# loki.net
KiCad netlist of a schematic drawn in EAGLE
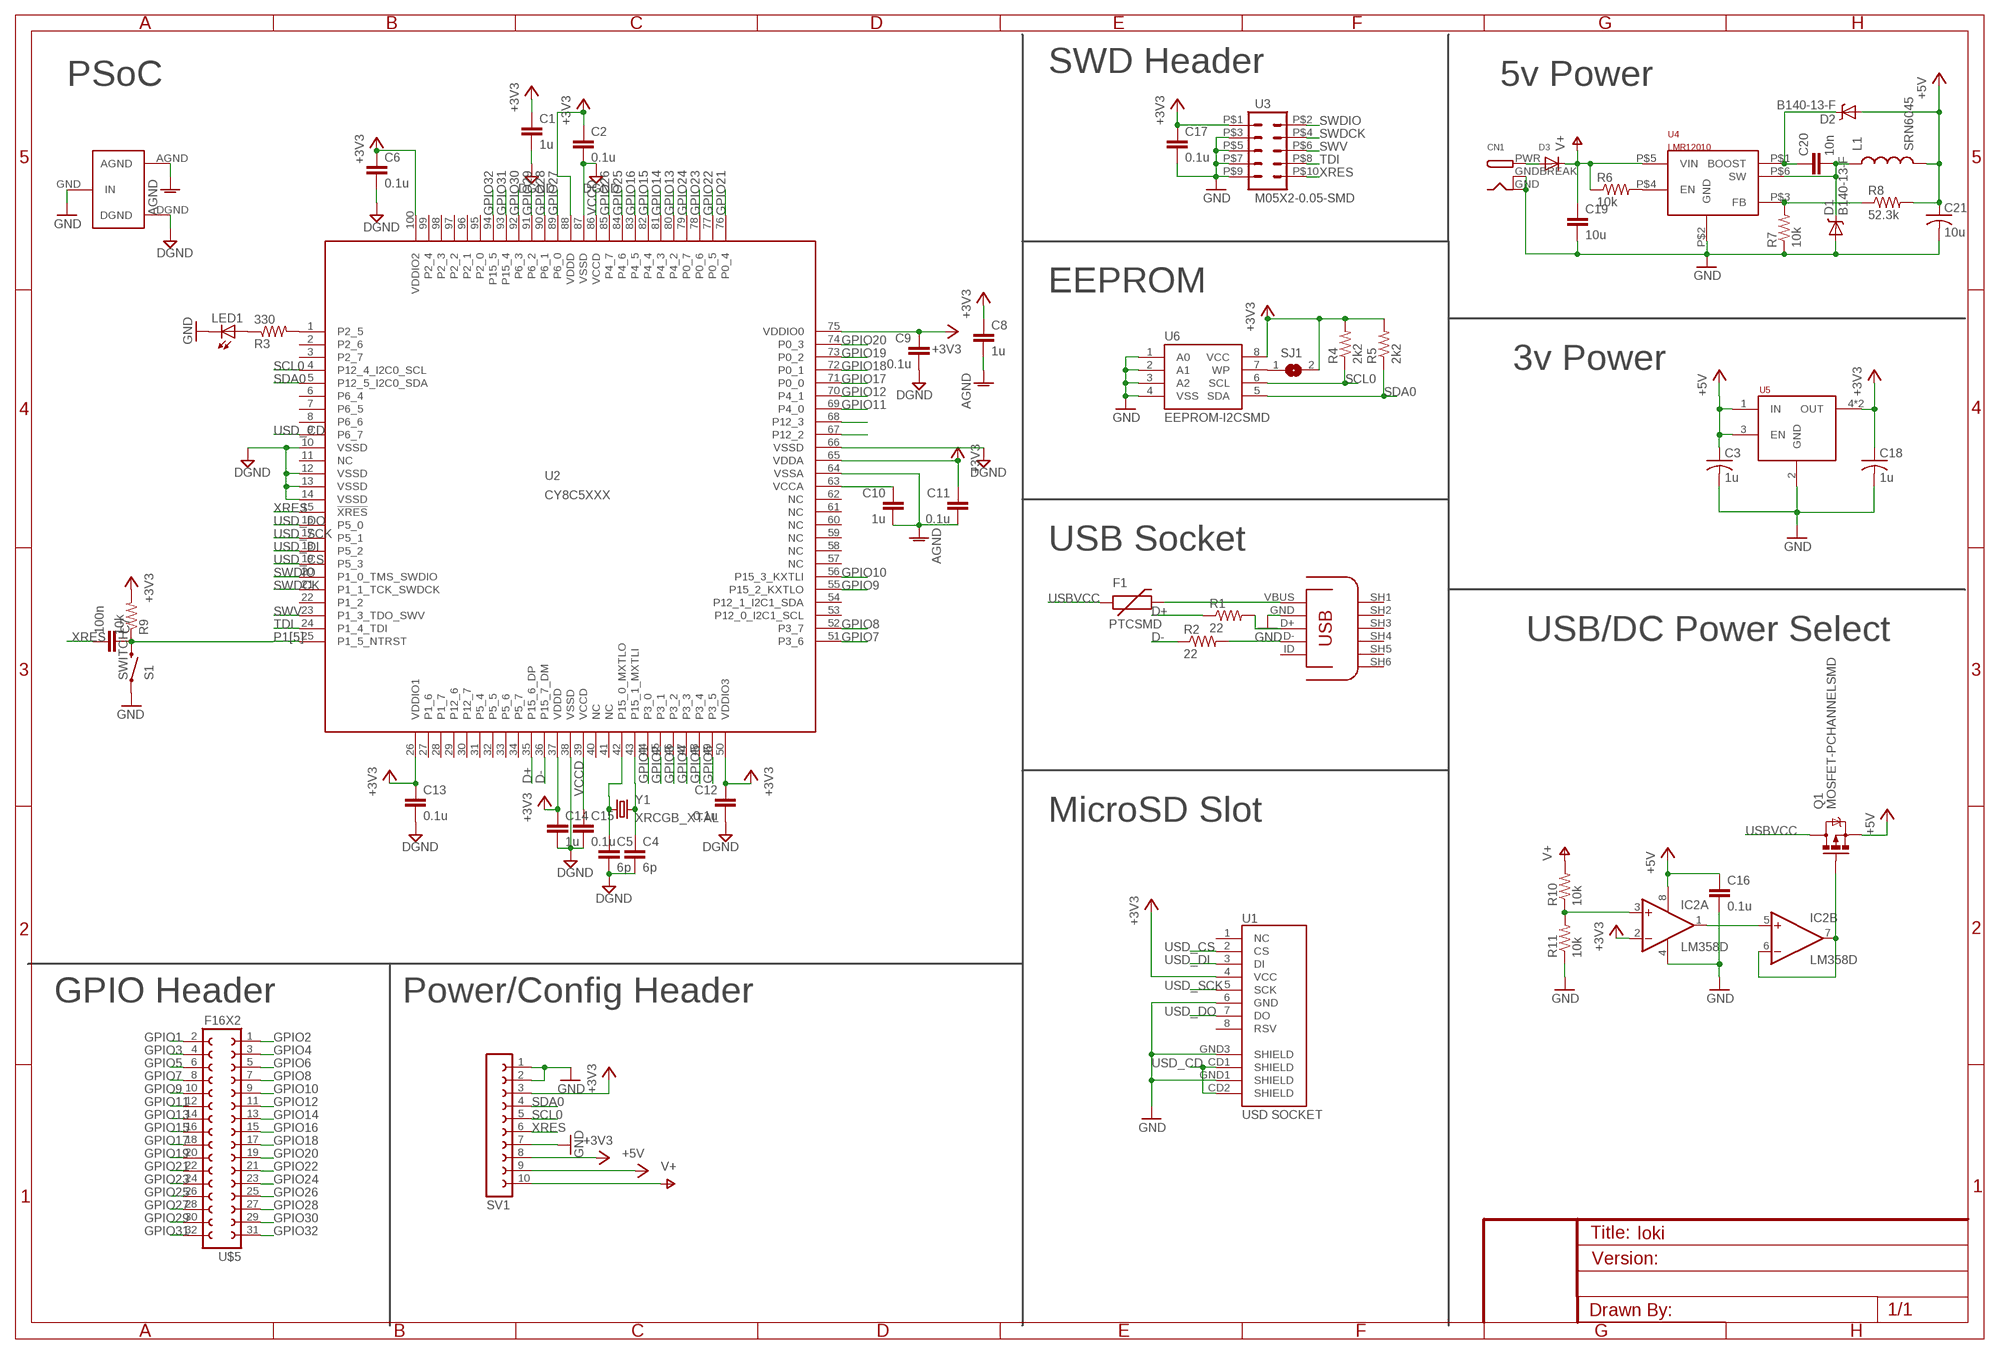
[diagram p0: schematic, sheet 1]

(export (version "E")
  (design (tool "Eeschema 10.0.6"))
  (components
    (comp (ref "C1")
      (value "1u")
      (footprint "eagle-import:C0603K")
      (libsource (lib "eagle-import") (part "C-EUC0603K"))
    )
    (comp (ref "C2")
      (value "0.1u")
      (footprint "eagle-import:C0603K")
      (libsource (lib "eagle-import") (part "C-EUC0603K"))
    )
    (comp (ref "C3")
      (value "1u")
      (footprint "eagle-import:C0603")
      (libsource (lib "eagle-import") (part "C-USC0603"))
    )
    (comp (ref "C4")
      (value "6p")
      (footprint "eagle-import:C0603K")
      (libsource (lib "eagle-import") (part "C-EUC0603K"))
    )
    (comp (ref "C5")
      (value "6p")
      (footprint "eagle-import:C0603K")
      (libsource (lib "eagle-import") (part "C-EUC0603K"))
    )
    (comp (ref "C6")
      (value "0.1u")
      (footprint "eagle-import:C0603K")
      (libsource (lib "eagle-import") (part "C-EUC0603K"))
    )
    (comp (ref "C7")
      (value "100n")
      (footprint "eagle-import:C0603K")
      (libsource (lib "eagle-import") (part "C-EUC0603K"))
    )
    (comp (ref "C8")
      (value "1u")
      (footprint "eagle-import:C0603K")
      (libsource (lib "eagle-import") (part "C-EUC0603K"))
    )
    (comp (ref "C9")
      (value "0.1u")
      (footprint "eagle-import:C0603K")
      (libsource (lib "eagle-import") (part "C-EUC0603K"))
    )
    (comp (ref "C10")
      (value "1u")
      (footprint "eagle-import:C0603K")
      (libsource (lib "eagle-import") (part "C-EUC0603K"))
    )
    (comp (ref "C11")
      (value "0.1u")
      (footprint "eagle-import:C0603K")
      (libsource (lib "eagle-import") (part "C-EUC0603K"))
    )
    (comp (ref "C12")
      (value "0.1u")
      (footprint "eagle-import:C0603K")
      (libsource (lib "eagle-import") (part "C-EUC0603K"))
    )
    (comp (ref "C13")
      (value "0.1u")
      (footprint "eagle-import:C0603K")
      (libsource (lib "eagle-import") (part "C-EUC0603K"))
    )
    (comp (ref "C14")
      (value "1u")
      (footprint "eagle-import:C0603K")
      (libsource (lib "eagle-import") (part "C-EUC0603K"))
    )
    (comp (ref "C15")
      (value "0.1u")
      (footprint "eagle-import:C0603K")
      (libsource (lib "eagle-import") (part "C-EUC0603K"))
    )
    (comp (ref "C16")
      (value "0.1u")
      (footprint "eagle-import:0603-CAP")
      (libsource (lib "eagle-import") (part "CAP0603-CAP"))
    )
    (comp (ref "C17")
      (value "0.1u")
      (footprint "eagle-import:C0603K")
      (libsource (lib "eagle-import") (part "C-EUC0603K"))
    )
    (comp (ref "C18")
      (value "1u")
      (footprint "eagle-import:C0603")
      (libsource (lib "eagle-import") (part "C-USC0603"))
    )
    (comp (ref "C19")
      (value "10u")
      (footprint "eagle-import:C1210")
      (libsource (lib "eagle-import") (part "C-EUC1210"))
    )
    (comp (ref "C20")
      (value "10n")
      (footprint "eagle-import:C0805")
      (libsource (lib "eagle-import") (part "C-EUC0805"))
    )
    (comp (ref "C21")
      (value "10u")
      (footprint "eagle-import:C1206")
      (libsource (lib "eagle-import") (part "C-USC1206"))
    )
    (comp (ref "CN1")
      (value "DCBARRELPTH")
      (footprint "eagle-import:DCJACK_2MM_PTH")
      (libsource (lib "eagle-import") (part "DCBARRELPTH"))
    )
    (comp (ref "D1")
      (value "B140-13-F")
      (footprint "eagle-import:SMA-DIODE")
      (libsource (lib "eagle-import") (part "DIODE-SCHOTTKY_"))
    )
    (comp (ref "D2")
      (value "B140-13-F")
      (footprint "eagle-import:SMA-DIODE")
      (libsource (lib "eagle-import") (part "DIODE-SCHOTTKY_"))
    )
    (comp (ref "D3")
      (value "DIODESMA")
      (footprint "eagle-import:SMADIODE")
      (libsource (lib "eagle-import") (part "DIODESMA"))
    )
    (comp (ref "F1")
      (value "PTCSMD")
      (footprint "eagle-import:PTC-1206")
      (libsource (lib "eagle-import") (part "PTCSMD"))
    )
    (comp (ref "IC2")
      (value "LM358D")
      (footprint "eagle-import:SO08")
      (libsource (lib "eagle-import") (part "LM358D"))
    )
    (comp (ref "L1")
      (value "SRN6045")
      (footprint "eagle-import:SRN6045")
      (libsource (lib "eagle-import") (part "SRN6045"))
    )
    (comp (ref "LED1")
      (value "LEDCHIP-LED0805")
      (footprint "eagle-import:CHIP-LED0805")
      (libsource (lib "eagle-import") (part "LEDCHIP-LED0805"))
    )
    (comp (ref "Q1")
      (value "MOSFET-PCHANNELSMD")
      (footprint "eagle-import:SOT23-3")
      (libsource (lib "eagle-import") (part "MOSFET-PCHANNELSMD"))
    )
    (comp (ref "R1")
      (value "22")
      (footprint "eagle-import:0603-RES")
      (libsource (lib "eagle-import") (part "RESISTOR0603-RES"))
    )
    (comp (ref "R2")
      (value "22")
      (footprint "eagle-import:0603-RES")
      (libsource (lib "eagle-import") (part "RESISTOR0603-RES"))
    )
    (comp (ref "R3")
      (value "330")
      (footprint "eagle-import:R0603")
      (libsource (lib "eagle-import") (part "R-US_R0603"))
    )
    (comp (ref "R4")
      (value "2k2")
      (footprint "eagle-import:R0603")
      (libsource (lib "eagle-import") (part "R-US_R0603"))
    )
    (comp (ref "R5")
      (value "2k2")
      (footprint "eagle-import:R0603")
      (libsource (lib "eagle-import") (part "R-US_R0603"))
    )
    (comp (ref "R6")
      (value "10k")
      (footprint "eagle-import:R0603")
      (libsource (lib "eagle-import") (part "R-US_R0603"))
    )
    (comp (ref "R7")
      (value "10k")
      (footprint "eagle-import:R0603")
      (libsource (lib "eagle-import") (part "R-US_R0603"))
    )
    (comp (ref "R8")
      (value "52.3k")
      (footprint "eagle-import:R0603")
      (libsource (lib "eagle-import") (part "R-US_R0603"))
    )
    (comp (ref "R9")
      (value "10k")
      (footprint "eagle-import:R0603")
      (libsource (lib "eagle-import") (part "R-US_R0603"))
    )
    (comp (ref "R10")
      (value "10k")
      (footprint "eagle-import:R0603")
      (libsource (lib "eagle-import") (part "R-US_R0603"))
    )
    (comp (ref "R11")
      (value "10k")
      (footprint "eagle-import:R0603")
      (libsource (lib "eagle-import") (part "R-US_R0603"))
    )
    (comp (ref "S1")
      (value "SWITCH")
      (footprint "eagle-import:TACTILE_SWITCH_SMD")
      (libsource (lib "eagle-import") (part "SWITCH-MOMENTARY-2SMD"))
    )
    (comp (ref "SJ1") (value "SJ") (footprint "eagle-import:SJ") (libsource (lib "eagle-import") (part "SJ")))
    (comp (ref "SV1")
      (value "FE10-1")
      (footprint "eagle-import:FE10")
      (libsource (lib "eagle-import") (part "FE10-1"))
    )
    (comp (ref "U$5")
      (value "F16X2")
      (footprint "eagle-import:FE16-2")
      (libsource (lib "eagle-import") (part "F16X2"))
    )
    (comp (ref "U$9")
      (value "GND_CONNECT")
      (footprint "eagle-import:GNDCONNECT")
      (libsource (lib "eagle-import") (part "GND_CONNECT"))
    )
    (comp (ref "U1")
      (value "USD SOCKET")
      (footprint "eagle-import:MICRO-SD-SOCKET-PP")
      (libsource (lib "eagle-import") (part "USD-SOCKETNEW"))
    )
    (comp (ref "U2")
      (value "CY8C5XXX")
      (footprint "eagle-import:TQFP-14X14-100")
      (fields (field (name "MPN") "CY8C5588AXI-060"))
      (libsource (lib "eagle-import") (part "CY8C5XXX-100PIN"))
    )
    (comp (ref "U3")
      (value "M05X2-0.05-SMD")
      (footprint "eagle-import:PINHD-2X5-0.05-SMD")
      (libsource (lib "eagle-import") (part "M05X2-0.05-SMD"))
    )
    (comp (ref "U4")
      (value "LMR12010")
      (footprint "eagle-import:TSOT-6")
      (libsource (lib "eagle-import") (part "LMR12010"))
    )
    (comp (ref "U5")
      (value "TLV702XX")
      (footprint "eagle-import:SOT23-5")
      (libsource (lib "eagle-import") (part "TLV702XX"))
    )
    (comp (ref "U6")
      (value "EEPROM-I2CSMD")
      (footprint "eagle-import:SO08")
      (libsource (lib "eagle-import") (part "EEPROM-I2CSMD"))
    )
    (comp (ref "U7")
      (value "MICROUSB")
      (footprint "eagle-import:USB-MICROB")
      (libsource (lib "eagle-import") (part "MICROUSB"))
    )
    (comp (ref "Y1")
      (value "XRCGB_XTAL")
      (footprint "eagle-import:XRCGB-XTAL")
      (libsource (lib "eagle-import") (part "XRCGB_XTAL"))
    )
  )
  (nets
    (net (code "1") (name "+3V3") (class "Default")
      (node (ref "C1") (pin "1") (pinfunction "1_1") (pintype "passive"))
      (node (ref "C11") (pin "1") (pinfunction "1_1") (pintype "passive"))
      (node (ref "C12") (pin "1") (pinfunction "1_1") (pintype "passive"))
      (node (ref "C13") (pin "1") (pinfunction "1_1") (pintype "passive"))
      (node (ref "C14") (pin "1") (pinfunction "1_1") (pintype "passive"))
      (node (ref "C17") (pin "1") (pinfunction "1_1") (pintype "passive"))
      (node (ref "C18") (pin "1") (pinfunction "1_1") (pintype "passive"))
      (node (ref "C2") (pin "1") (pinfunction "1_1") (pintype "passive"))
      (node (ref "C6") (pin "1") (pinfunction "1_1") (pintype "passive"))
      (node (ref "C8") (pin "1") (pinfunction "1_1") (pintype "passive"))
      (node (ref "C9") (pin "1") (pinfunction "1_1") (pintype "passive"))
      (node (ref "IC2") (pin "2") (pinfunction "-IN_2") (pintype "input"))
      (node (ref "R4") (pin "2") (pinfunction "2_2") (pintype "passive"))
      (node (ref "R5") (pin "2") (pinfunction "2_2") (pintype "passive"))
      (node (ref "R9") (pin "2") (pinfunction "2_2") (pintype "passive"))
      (node (ref "SJ1") (pin "2") (pinfunction "2_2") (pintype "passive"))
      (node (ref "SV1") (pin "3") (pinfunction "3_3") (pintype "passive"))
      (node (ref "SV1") (pin "8") (pinfunction "8_8") (pintype "passive"))
      (node (ref "U1") (pin "4") (pinfunction "VCC_4") (pintype "bidirectional"))
      (node (ref "U2") (pin "100") (pinfunction "VDDIO2_100") (pintype "passive"))
      (node (ref "U2") (pin "26") (pinfunction "VDDIO1_26") (pintype "passive"))
      (node (ref "U2") (pin "37") (pinfunction "VDDD_37") (pintype "passive"))
      (node (ref "U2") (pin "50") (pinfunction "VDDIO3_50") (pintype "passive"))
      (node (ref "U2") (pin "65") (pinfunction "VDDA_65") (pintype "passive"))
      (node (ref "U2") (pin "75") (pinfunction "VDDIO0_75") (pintype "passive"))
      (node (ref "U2") (pin "88") (pinfunction "VDDD_88") (pintype "passive"))
      (node (ref "U3") (pin "P$1") (pinfunction "1_P$1") (pintype "passive"))
      (node (ref "U5") (pin "4") (pinfunction "OUT_4") (pintype "power_in"))
      (node (ref "U5") (pin "5") (pinfunction "OUT_5") (pintype "power_in"))
      (node (ref "U6") (pin "8") (pinfunction "VCC_8") (pintype "power_in"))
    )
    (net (code "2") (name "+5V") (class "Default")
      (node (ref "C16") (pin "1") (pinfunction "1_1") (pintype "passive"))
      (node (ref "C21") (pin "1") (pinfunction "1_1") (pintype "passive"))
      (node (ref "C3") (pin "1") (pinfunction "1_1") (pintype "passive"))
      (node (ref "D2") (pin "A") (pinfunction "A_A") (pintype "passive"))
      (node (ref "IC2") (pin "8") (pinfunction "V+_8") (pintype "power_in"))
      (node (ref "L1") (pin "P$2") (pinfunction "2_P$2") (pintype "passive"))
      (node (ref "Q1") (pin "2") (pinfunction "S_2") (pintype "passive"))
      (node (ref "R8") (pin "2") (pinfunction "2_2") (pintype "passive"))
      (node (ref "SV1") (pin "9") (pinfunction "9_9") (pintype "passive"))
      (node (ref "U5") (pin "1") (pinfunction "IN_1") (pintype "power_in"))
      (node (ref "U5") (pin "3") (pinfunction "EN_3") (pintype "input"))
    )
    (net (code "3") (name "/D+") (class "Default")
      (node (ref "R1") (pin "1") (pinfunction "1_1") (pintype "passive"))
      (node (ref "U2") (pin "35") (pinfunction "P15_6_DP_35") (pintype "passive"))
    )
    (net (code "4") (name "/D-") (class "Default")
      (node (ref "R2") (pin "1") (pinfunction "1_1") (pintype "passive"))
      (node (ref "U2") (pin "36") (pinfunction "P15_7_DM_36") (pintype "passive"))
    )
    (net (code "5") (name "/GPIO1") (class "Default")
      (node (ref "U$5") (pin "2") (pinfunction "2_2") (pintype "passive"))
      (node (ref "U2") (pin "44") (pinfunction "P3_0_44") (pintype "passive"))
    )
    (net (code "6") (name "/GPIO2") (class "Default")
      (node (ref "U$5") (pin "1") (pinfunction "1_1") (pintype "passive"))
      (node (ref "U2") (pin "45") (pinfunction "P3_1_45") (pintype "passive"))
    )
    (net (code "7") (name "/GPIO3") (class "Default")
      (node (ref "U$5") (pin "4") (pinfunction "4_4") (pintype "passive"))
      (node (ref "U2") (pin "46") (pinfunction "P3_2_46") (pintype "passive"))
    )
    (net (code "8") (name "/GPIO4") (class "Default")
      (node (ref "U$5") (pin "3") (pinfunction "3_3") (pintype "passive"))
      (node (ref "U2") (pin "47") (pinfunction "P3_3_47") (pintype "passive"))
    )
    (net (code "9") (name "/GPIO5") (class "Default")
      (node (ref "U$5") (pin "6") (pinfunction "6_6") (pintype "passive"))
      (node (ref "U2") (pin "48") (pinfunction "P3_4_48") (pintype "passive"))
    )
    (net (code "10") (name "/GPIO6") (class "Default")
      (node (ref "U$5") (pin "5") (pinfunction "5_5") (pintype "passive"))
      (node (ref "U2") (pin "49") (pinfunction "P3_5_49") (pintype "passive"))
    )
    (net (code "11") (name "/GPIO7") (class "Default")
      (node (ref "U$5") (pin "8") (pinfunction "8_8") (pintype "passive"))
      (node (ref "U2") (pin "51") (pinfunction "P3_6_51") (pintype "passive"))
    )
    (net (code "12") (name "/GPIO8") (class "Default")
      (node (ref "U$5") (pin "7") (pinfunction "7_7") (pintype "passive"))
      (node (ref "U2") (pin "52") (pinfunction "P3_7_52") (pintype "passive"))
    )
    (net (code "13") (name "/GPIO9") (class "Default")
      (node (ref "U$5") (pin "10") (pinfunction "10_10") (pintype "passive"))
      (node (ref "U2") (pin "55") (pinfunction "P15_2_KXTLO_55") (pintype "passive"))
    )
    (net (code "14") (name "/GPIO10") (class "Default")
      (node (ref "U$5") (pin "9") (pinfunction "9_9") (pintype "passive"))
      (node (ref "U2") (pin "56") (pinfunction "P15_3_KXTLI_56") (pintype "passive"))
    )
    (net (code "15") (name "/GPIO11") (class "Default")
      (node (ref "U$5") (pin "12") (pinfunction "12_12") (pintype "passive"))
      (node (ref "U2") (pin "69") (pinfunction "P4_0_69") (pintype "passive"))
    )
    (net (code "16") (name "/GPIO12") (class "Default")
      (node (ref "U$5") (pin "11") (pinfunction "11_11") (pintype "passive"))
      (node (ref "U2") (pin "70") (pinfunction "P4_1_70") (pintype "passive"))
    )
    (net (code "17") (name "/GPIO13") (class "Default")
      (node (ref "U$5") (pin "14") (pinfunction "14_14") (pintype "passive"))
      (node (ref "U2") (pin "80") (pinfunction "P4_2_80") (pintype "passive"))
    )
    (net (code "18") (name "/GPIO14") (class "Default")
      (node (ref "U$5") (pin "13") (pinfunction "13_13") (pintype "passive"))
      (node (ref "U2") (pin "81") (pinfunction "P4_3_81") (pintype "passive"))
    )
    (net (code "19") (name "/GPIO15") (class "Default")
      (node (ref "U$5") (pin "16") (pinfunction "16_16") (pintype "passive"))
      (node (ref "U2") (pin "82") (pinfunction "P4_4_82") (pintype "passive"))
    )
    (net (code "20") (name "/GPIO16") (class "Default")
      (node (ref "U$5") (pin "15") (pinfunction "15_15") (pintype "passive"))
      (node (ref "U2") (pin "83") (pinfunction "P4_5_83") (pintype "passive"))
    )
    (net (code "21") (name "/GPIO17") (class "Default")
      (node (ref "U$5") (pin "18") (pinfunction "18_18") (pintype "passive"))
      (node (ref "U2") (pin "71") (pinfunction "P0_0_71") (pintype "passive"))
    )
    (net (code "22") (name "/GPIO18") (class "Default")
      (node (ref "U$5") (pin "17") (pinfunction "17_17") (pintype "passive"))
      (node (ref "U2") (pin "72") (pinfunction "P0_1_72") (pintype "passive"))
    )
    (net (code "23") (name "/GPIO19") (class "Default")
      (node (ref "U$5") (pin "20") (pinfunction "20_20") (pintype "passive"))
      (node (ref "U2") (pin "73") (pinfunction "P0_2_73") (pintype "passive"))
    )
    (net (code "24") (name "/GPIO20") (class "Default")
      (node (ref "U$5") (pin "19") (pinfunction "19_19") (pintype "passive"))
      (node (ref "U2") (pin "74") (pinfunction "P0_3_74") (pintype "passive"))
    )
    (net (code "25") (name "/GPIO21") (class "Default")
      (node (ref "U$5") (pin "22") (pinfunction "22_22") (pintype "passive"))
      (node (ref "U2") (pin "76") (pinfunction "P0_4_76") (pintype "passive"))
    )
    (net (code "26") (name "/GPIO22") (class "Default")
      (node (ref "U$5") (pin "21") (pinfunction "21_21") (pintype "passive"))
      (node (ref "U2") (pin "77") (pinfunction "P0_5_77") (pintype "passive"))
    )
    (net (code "27") (name "/GPIO23") (class "Default")
      (node (ref "U$5") (pin "24") (pinfunction "24_24") (pintype "passive"))
      (node (ref "U2") (pin "78") (pinfunction "P0_6_78") (pintype "passive"))
    )
    (net (code "28") (name "/GPIO24") (class "Default")
      (node (ref "U$5") (pin "23") (pinfunction "23_23") (pintype "passive"))
      (node (ref "U2") (pin "79") (pinfunction "P0_7_79") (pintype "passive"))
    )
    (net (code "29") (name "/GPIO25") (class "Default")
      (node (ref "U$5") (pin "26") (pinfunction "26_26") (pintype "passive"))
      (node (ref "U2") (pin "84") (pinfunction "P4_6_84") (pintype "passive"))
    )
    (net (code "30") (name "/GPIO26") (class "Default")
      (node (ref "U$5") (pin "25") (pinfunction "25_25") (pintype "passive"))
      (node (ref "U2") (pin "85") (pinfunction "P4_7_85") (pintype "passive"))
    )
    (net (code "31") (name "/GPIO27") (class "Default")
      (node (ref "U$5") (pin "28") (pinfunction "28_28") (pintype "passive"))
      (node (ref "U2") (pin "89") (pinfunction "P6_0_89") (pintype "passive"))
    )
    (net (code "32") (name "/GPIO28") (class "Default")
      (node (ref "U$5") (pin "27") (pinfunction "27_27") (pintype "passive"))
      (node (ref "U2") (pin "90") (pinfunction "P6_1_90") (pintype "passive"))
    )
    (net (code "33") (name "/GPIO29") (class "Default")
      (node (ref "U$5") (pin "30") (pinfunction "30_30") (pintype "passive"))
      (node (ref "U2") (pin "91") (pinfunction "P6_2_91") (pintype "passive"))
    )
    (net (code "34") (name "/GPIO30") (class "Default")
      (node (ref "U$5") (pin "29") (pinfunction "29_29") (pintype "passive"))
      (node (ref "U2") (pin "92") (pinfunction "P6_3_92") (pintype "passive"))
    )
    (net (code "35") (name "/GPIO31") (class "Default")
      (node (ref "U$5") (pin "32") (pinfunction "32_32") (pintype "passive"))
      (node (ref "U2") (pin "93") (pinfunction "P15_4_93") (pintype "passive"))
    )
    (net (code "36") (name "/GPIO32") (class "Default")
      (node (ref "U$5") (pin "31") (pinfunction "31_31") (pintype "passive"))
      (node (ref "U2") (pin "94") (pinfunction "P15_5_94") (pintype "passive"))
    )
    (net (code "37") (name "/P1[5]") (class "Default")
      (node (ref "C7") (pin "1") (pinfunction "1_1") (pintype "passive"))
      (node (ref "R9") (pin "1") (pinfunction "1_1") (pintype "passive"))
      (node (ref "S1") (pin "3") (pinfunction "2_3") (pintype "passive"))
      (node (ref "U2") (pin "25") (pinfunction "P1_5_NTRST_25") (pintype "passive"))
    )
    (net (code "38") (name "/SCL0") (class "Default")
      (node (ref "R4") (pin "1") (pinfunction "1_1") (pintype "passive"))
      (node (ref "SV1") (pin "5") (pinfunction "5_5") (pintype "passive"))
      (node (ref "U2") (pin "4") (pinfunction "P12_4_I2C0_SCL_4") (pintype "passive"))
      (node (ref "U6") (pin "6") (pinfunction "SCL_6") (pintype "bidirectional"))
    )
    (net (code "39") (name "/SDA0") (class "Default")
      (node (ref "R5") (pin "1") (pinfunction "1_1") (pintype "passive"))
      (node (ref "SV1") (pin "4") (pinfunction "4_4") (pintype "passive"))
      (node (ref "U2") (pin "5") (pinfunction "P12_5_I2C0_SDA_5") (pintype "passive"))
      (node (ref "U6") (pin "5") (pinfunction "SDA_5") (pintype "bidirectional"))
    )
    (net (code "40") (name "/SWDCK") (class "Default")
      (node (ref "U2") (pin "21") (pinfunction "P1_1_TCK_SWDCK_21") (pintype "passive"))
      (node (ref "U3") (pin "P$4") (pinfunction "4_P$4") (pintype "passive"))
    )
    (net (code "41") (name "/SWDIO") (class "Default")
      (node (ref "U2") (pin "20") (pinfunction "P1_0_TMS_SWDIO_20") (pintype "passive"))
      (node (ref "U3") (pin "P$2") (pinfunction "2_P$2") (pintype "passive"))
    )
    (net (code "42") (name "/SWV") (class "Default")
      (node (ref "U2") (pin "23") (pinfunction "P1_3_TDO_SWV_23") (pintype "passive"))
      (node (ref "U3") (pin "P$6") (pinfunction "6_P$6") (pintype "passive"))
    )
    (net (code "43") (name "/TDI") (class "Default")
      (node (ref "U2") (pin "24") (pinfunction "P1_4_TDI_24") (pintype "passive"))
      (node (ref "U3") (pin "P$8") (pinfunction "8_P$8") (pintype "passive"))
    )
    (net (code "44") (name "/USBVCC") (class "Default")
      (node (ref "F1") (pin "1") (pinfunction "1_1") (pintype "bidirectional"))
      (node (ref "Q1") (pin "3") (pinfunction "D_3") (pintype "passive"))
    )
    (net (code "45") (name "/USD_CD") (class "Default")
      (node (ref "U1") (pin "CD1") (pinfunction "SHIELD_CD1") (pintype "bidirectional"))
      (node (ref "U1") (pin "CD2") (pinfunction "SHIELD_CD2") (pintype "bidirectional"))
      (node (ref "U2") (pin "9") (pinfunction "P6_7_9") (pintype "passive"))
    )
    (net (code "46") (name "/USD_CS") (class "Default")
      (node (ref "U1") (pin "2") (pinfunction "CS_2") (pintype "bidirectional"))
      (node (ref "U2") (pin "19") (pinfunction "P5_3_19") (pintype "passive"))
    )
    (net (code "47") (name "/USD_DI") (class "Default")
      (node (ref "U1") (pin "3") (pinfunction "DI_3") (pintype "bidirectional"))
      (node (ref "U2") (pin "18") (pinfunction "P5_2_18") (pintype "passive"))
    )
    (net (code "48") (name "/USD_DO") (class "Default")
      (node (ref "U1") (pin "7") (pinfunction "DO_7") (pintype "bidirectional"))
      (node (ref "U2") (pin "16") (pinfunction "P5_0_16") (pintype "passive"))
    )
    (net (code "49") (name "/USD_SCK") (class "Default")
      (node (ref "U1") (pin "5") (pinfunction "SCK_5") (pintype "bidirectional"))
      (node (ref "U2") (pin "17") (pinfunction "P5_1_17") (pintype "passive"))
    )
    (net (code "50") (name "/VCCD") (class "Default")
      (node (ref "C15") (pin "1") (pinfunction "1_1") (pintype "passive"))
      (node (ref "U2") (pin "39") (pinfunction "VCCD_39") (pintype "passive"))
      (node (ref "U2") (pin "86") (pinfunction "VCCD_86") (pintype "passive"))
    )
    (net (code "51") (name "/XRES") (class "Default")
      (node (ref "C7") (pin "2") (pinfunction "2_2") (pintype "passive"))
      (node (ref "SV1") (pin "6") (pinfunction "6_6") (pintype "passive"))
      (node (ref "U2") (pin "15") (pinfunction "~{XRES}_15") (pintype "passive"))
      (node (ref "U3") (pin "P$10") (pinfunction "10_P$10") (pintype "passive"))
    )
    (net (code "52") (name "AGND") (class "Default")
      (node (ref "C10") (pin "2") (pinfunction "2_2") (pintype "passive"))
      (node (ref "C11") (pin "2") (pinfunction "2_2") (pintype "passive"))
      (node (ref "C8") (pin "2") (pinfunction "2_2") (pintype "passive"))
      (node (ref "U$9") (pin "AGND") (pinfunction "AGND_AGND") (pintype "bidirectional"))
      (node (ref "U2") (pin "64") (pinfunction "VSSA_64") (pintype "passive"))
    )
    (net (code "53") (name "DGND") (class "Default")
      (node (ref "C1") (pin "2") (pinfunction "2_2") (pintype "passive"))
      (node (ref "C12") (pin "2") (pinfunction "2_2") (pintype "passive"))
      (node (ref "C13") (pin "2") (pinfunction "2_2") (pintype "passive"))
      (node (ref "C14") (pin "2") (pinfunction "2_2") (pintype "passive"))
      (node (ref "C15") (pin "2") (pinfunction "2_2") (pintype "passive"))
      (node (ref "C2") (pin "2") (pinfunction "2_2") (pintype "passive"))
      (node (ref "C4") (pin "2") (pinfunction "2_2") (pintype "passive"))
      (node (ref "C5") (pin "2") (pinfunction "2_2") (pintype "passive"))
      (node (ref "C6") (pin "2") (pinfunction "2_2") (pintype "passive"))
      (node (ref "C9") (pin "2") (pinfunction "2_2") (pintype "passive"))
      (node (ref "U$9") (pin "DGND") (pinfunction "DGND_DGND") (pintype "bidirectional"))
      (node (ref "U2") (pin "10") (pinfunction "VSSD_10") (pintype "passive"))
      (node (ref "U2") (pin "12") (pinfunction "VSSD_12") (pintype "passive"))
      (node (ref "U2") (pin "13") (pinfunction "VSSD_13") (pintype "passive"))
      (node (ref "U2") (pin "14") (pinfunction "VSSD_14") (pintype "passive"))
      (node (ref "U2") (pin "38") (pinfunction "VSSD_38") (pintype "passive"))
      (node (ref "U2") (pin "66") (pinfunction "VSSD_66") (pintype "passive"))
      (node (ref "U2") (pin "87") (pinfunction "VSSD_87") (pintype "passive"))
    )
    (net (code "54") (name "GND") (class "Default")
      (node (ref "C16") (pin "2") (pinfunction "2_2") (pintype "passive"))
      (node (ref "C17") (pin "2") (pinfunction "2_2") (pintype "passive"))
      (node (ref "C18") (pin "2") (pinfunction "2_2") (pintype "passive"))
      (node (ref "C19") (pin "2") (pinfunction "2_2") (pintype "passive"))
      (node (ref "C21") (pin "2") (pinfunction "2_2") (pintype "passive"))
      (node (ref "C3") (pin "2") (pinfunction "2_2") (pintype "passive"))
      (node (ref "CN1") (pin "GND") (pinfunction "GND_GND") (pintype "power_in"))
      (node (ref "CN1") (pin "GNDBREAK") (pinfunction "GNDBREAK_GNDBREAK") (pintype "power_in"))
      (node (ref "D1") (pin "A") (pinfunction "A_A") (pintype "passive"))
      (node (ref "IC2") (pin "4") (pinfunction "V-_4") (pintype "power_in"))
      (node (ref "LED1") (pin "C") (pinfunction "C_C") (pintype "passive"))
      (node (ref "R11") (pin "1") (pinfunction "1_1") (pintype "passive"))
      (node (ref "R7") (pin "1") (pinfunction "1_1") (pintype "passive"))
      (node (ref "S1") (pin "1") (pinfunction "1_1") (pintype "passive"))
      (node (ref "SV1") (pin "1") (pinfunction "1_1") (pintype "passive"))
      (node (ref "SV1") (pin "2") (pinfunction "2_2") (pintype "passive"))
      (node (ref "SV1") (pin "7") (pinfunction "7_7") (pintype "passive"))
      (node (ref "U$9") (pin "GND") (pinfunction "IN_GND") (pintype "bidirectional"))
      (node (ref "U1") (pin "6") (pinfunction "GND_6") (pintype "bidirectional"))
      (node (ref "U1") (pin "GND1") (pinfunction "SHIELD_GND1") (pintype "bidirectional"))
      (node (ref "U1") (pin "GND3") (pinfunction "SHIELD_GND3") (pintype "bidirectional"))
      (node (ref "U3") (pin "P$3") (pinfunction "3_P$3") (pintype "passive"))
      (node (ref "U3") (pin "P$5") (pinfunction "5_P$5") (pintype "passive"))
      (node (ref "U3") (pin "P$7") (pinfunction "7_P$7") (pintype "passive"))
      (node (ref "U3") (pin "P$9") (pinfunction "9_P$9") (pintype "passive"))
      (node (ref "U4") (pin "P$2") (pinfunction "GND_P$2") (pintype "power_in"))
      (node (ref "U5") (pin "2") (pinfunction "GND_2") (pintype "power_in"))
      (node (ref "U6") (pin "1") (pinfunction "A0_1") (pintype "bidirectional"))
      (node (ref "U6") (pin "2") (pinfunction "A1_2") (pintype "bidirectional"))
      (node (ref "U6") (pin "3") (pinfunction "A2_3") (pintype "bidirectional"))
      (node (ref "U6") (pin "4") (pinfunction "VSS_4") (pintype "power_in"))
      (node (ref "U7") (pin "GND") (pinfunction "GND_GND") (pintype "bidirectional"))
    )
    (net (code "55") (name "Net-(CN1-PadPWR)") (class "Default")
      (node (ref "CN1") (pin "PWR") (pinfunction "PWR_PWR") (pintype "power_in"))
      (node (ref "D3") (pin "A") (pinfunction "A_A") (pintype "passive"))
    )
    (net (code "56") (name "Net-(IC2A-+IN)") (class "Default")
      (node (ref "IC2") (pin "3") (pinfunction "+IN_3") (pintype "input"))
      (node (ref "R10") (pin "1") (pinfunction "1_1") (pintype "passive"))
      (node (ref "R11") (pin "2") (pinfunction "2_2") (pintype "passive"))
    )
    (net (code "57") (name "Net-(IC2A-OUT)") (class "Default")
      (node (ref "IC2") (pin "1") (pinfunction "OUT_1") (pintype "output"))
      (node (ref "IC2") (pin "5") (pinfunction "+IN_5") (pintype "input"))
    )
    (net (code "58") (name "Net-(IC2B--IN)") (class "Default")
      (node (ref "IC2") (pin "6") (pinfunction "-IN_6") (pintype "input"))
      (node (ref "IC2") (pin "7") (pinfunction "OUT_7") (pintype "output"))
      (node (ref "Q1") (pin "1") (pinfunction "G_1") (pintype "passive"))
    )
    (net (code "59") (name "Net-(L1-1)") (class "Default")
      (node (ref "C20") (pin "2") (pinfunction "2_2") (pintype "passive"))
      (node (ref "D1") (pin "C") (pinfunction "C_C") (pintype "passive"))
      (node (ref "L1") (pin "P$1") (pinfunction "1_P$1") (pintype "passive"))
      (node (ref "U4") (pin "P$6") (pinfunction "SW_P$6") (pintype "power_in"))
    )
    (net (code "60") (name "Net-(LED1-PadA)") (class "Default")
      (node (ref "LED1") (pin "A") (pinfunction "A_A") (pintype "passive"))
      (node (ref "R3") (pin "1") (pinfunction "1_1") (pintype "passive"))
    )
    (net (code "61") (name "Net-(R1-Pad2)") (class "Default")
      (node (ref "R1") (pin "2") (pinfunction "2_2") (pintype "passive"))
      (node (ref "U7") (pin "D+") (pinfunction "D+_D+") (pintype "bidirectional"))
    )
    (net (code "62") (name "Net-(R2-Pad2)") (class "Default")
      (node (ref "R2") (pin "2") (pinfunction "2_2") (pintype "passive"))
      (node (ref "U7") (pin "D-") (pinfunction "D-_D-") (pintype "bidirectional"))
    )
    (net (code "63") (name "Net-(U2-P2_5)") (class "Default")
      (node (ref "R3") (pin "2") (pinfunction "2_2") (pintype "passive"))
      (node (ref "U2") (pin "1") (pinfunction "P2_5_1") (pintype "passive"))
    )
    (net (code "64") (name "Net-(U2-P15_0_MXTLO)") (class "Default")
      (node (ref "C5") (pin "1") (pinfunction "1_1") (pintype "passive"))
      (node (ref "U2") (pin "42") (pinfunction "P15_0_MXTLO_42") (pintype "passive"))
      (node (ref "Y1") (pin "1") (pinfunction "1_1") (pintype "passive"))
    )
    (net (code "65") (name "Net-(U2-P15_1_MXTLI)") (class "Default")
      (node (ref "C4") (pin "1") (pinfunction "1_1") (pintype "passive"))
      (node (ref "U2") (pin "43") (pinfunction "P15_1_MXTLI_43") (pintype "passive"))
      (node (ref "Y1") (pin "2") (pinfunction "2_2") (pintype "passive"))
    )
    (net (code "66") (name "Net-(U2-VCCA)") (class "Default")
      (node (ref "C10") (pin "1") (pinfunction "1_1") (pintype "passive"))
      (node (ref "U2") (pin "63") (pinfunction "VCCA_63") (pintype "passive"))
    )
    (net (code "67") (name "Net-(U4-BOOST)") (class "Default")
      (node (ref "C20") (pin "1") (pinfunction "1_1") (pintype "passive"))
      (node (ref "D2") (pin "C") (pinfunction "C_C") (pintype "passive"))
      (node (ref "U4") (pin "P$1") (pinfunction "BOOST_P$1") (pintype "input"))
    )
    (net (code "68") (name "Net-(U4-EN)") (class "Default")
      (node (ref "R6") (pin "2") (pinfunction "2_2") (pintype "passive"))
      (node (ref "U4") (pin "P$4") (pinfunction "EN_P$4") (pintype "input"))
    )
    (net (code "69") (name "Net-(U4-FB)") (class "Default")
      (node (ref "R7") (pin "2") (pinfunction "2_2") (pintype "passive"))
      (node (ref "R8") (pin "1") (pinfunction "1_1") (pintype "passive"))
      (node (ref "U4") (pin "P$3") (pinfunction "FB_P$3") (pintype "input"))
    )
    (net (code "70") (name "Net-(U6-WP)") (class "Default")
      (node (ref "SJ1") (pin "1") (pinfunction "1_1") (pintype "passive"))
      (node (ref "U6") (pin "7") (pinfunction "WP_7") (pintype "bidirectional"))
    )
    (net (code "71") (name "Net-(U7-VCC)") (class "Default")
      (node (ref "F1") (pin "2") (pinfunction "2_2") (pintype "bidirectional"))
      (node (ref "U7") (pin "VBUS") (pinfunction "VCC_VBUS") (pintype "bidirectional"))
    )
    (net (code "72") (name "V+") (class "Default")
      (node (ref "C19") (pin "1") (pinfunction "1_1") (pintype "passive"))
      (node (ref "D3") (pin "C") (pinfunction "C_C") (pintype "passive"))
      (node (ref "R10") (pin "2") (pinfunction "2_2") (pintype "passive"))
      (node (ref "R6") (pin "1") (pinfunction "1_1") (pintype "passive"))
      (node (ref "SV1") (pin "10") (pinfunction "10_10") (pintype "passive"))
      (node (ref "U4") (pin "P$5") (pinfunction "VIN_P$5") (pintype "power_in"))
    )
    (net (code "73") (name "unconnected-(U1-NC-Pad1)") (class "Default")
      (node (ref "U1") (pin "1") (pinfunction "NC_1") (pintype "bidirectional"))
    )
    (net (code "74") (name "unconnected-(U1-RSV-Pad8)") (class "Default")
      (node (ref "U1") (pin "8") (pinfunction "RSV_8") (pintype "bidirectional"))
    )
    (net (code "75") (name "unconnected-(U2-NC-Pad11)") (class "Default")
      (node (ref "U2") (pin "11") (pinfunction "NC_11") (pintype "passive"))
    )
    (net (code "76") (name "unconnected-(U2-NC-Pad40)") (class "Default")
      (node (ref "U2") (pin "40") (pinfunction "NC_40") (pintype "passive"))
    )
    (net (code "77") (name "unconnected-(U2-NC-Pad41)") (class "Default")
      (node (ref "U2") (pin "41") (pinfunction "NC_41") (pintype "passive"))
    )
    (net (code "78") (name "unconnected-(U2-NC-Pad57)") (class "Default")
      (node (ref "U2") (pin "57") (pinfunction "NC_57") (pintype "passive"))
    )
    (net (code "79") (name "unconnected-(U2-NC-Pad58)") (class "Default")
      (node (ref "U2") (pin "58") (pinfunction "NC_58") (pintype "passive"))
    )
    (net (code "80") (name "unconnected-(U2-NC-Pad59)") (class "Default")
      (node (ref "U2") (pin "59") (pinfunction "NC_59") (pintype "passive"))
    )
    (net (code "81") (name "unconnected-(U2-NC-Pad60)") (class "Default")
      (node (ref "U2") (pin "60") (pinfunction "NC_60") (pintype "passive"))
    )
    (net (code "82") (name "unconnected-(U2-NC-Pad61)") (class "Default")
      (node (ref "U2") (pin "61") (pinfunction "NC_61") (pintype "passive"))
    )
    (net (code "83") (name "unconnected-(U2-NC-Pad62)") (class "Default")
      (node (ref "U2") (pin "62") (pinfunction "NC_62") (pintype "passive"))
    )
    (net (code "84") (name "unconnected-(U2-P1_2-Pad22)") (class "Default")
      (node (ref "U2") (pin "22") (pinfunction "P1_2_22") (pintype "passive"))
    )
    (net (code "85") (name "unconnected-(U2-P1_6-Pad27)") (class "Default")
      (node (ref "U2") (pin "27") (pinfunction "P1_6_27") (pintype "passive"))
    )
    (net (code "86") (name "unconnected-(U2-P1_7-Pad28)") (class "Default")
      (node (ref "U2") (pin "28") (pinfunction "P1_7_28") (pintype "passive"))
    )
    (net (code "87") (name "unconnected-(U2-P2_0-Pad95)") (class "Default")
      (node (ref "U2") (pin "95") (pinfunction "P2_0_95") (pintype "passive"))
    )
    (net (code "88") (name "unconnected-(U2-P2_1-Pad96)") (class "Default")
      (node (ref "U2") (pin "96") (pinfunction "P2_1_96") (pintype "passive"))
    )
    (net (code "89") (name "unconnected-(U2-P2_2-Pad97)") (class "Default")
      (node (ref "U2") (pin "97") (pinfunction "P2_2_97") (pintype "passive"))
    )
    (net (code "90") (name "unconnected-(U2-P2_3-Pad98)") (class "Default")
      (node (ref "U2") (pin "98") (pinfunction "P2_3_98") (pintype "passive"))
    )
    (net (code "91") (name "unconnected-(U2-P2_4-Pad99)") (class "Default")
      (node (ref "U2") (pin "99") (pinfunction "P2_4_99") (pintype "passive"))
    )
    (net (code "92") (name "unconnected-(U2-P2_6-Pad2)") (class "Default")
      (node (ref "U2") (pin "2") (pinfunction "P2_6_2") (pintype "passive"))
    )
    (net (code "93") (name "unconnected-(U2-P2_7-Pad3)") (class "Default")
      (node (ref "U2") (pin "3") (pinfunction "P2_7_3") (pintype "passive"))
    )
    (net (code "94") (name "unconnected-(U2-P5_4-Pad31)") (class "Default")
      (node (ref "U2") (pin "31") (pinfunction "P5_4_31") (pintype "passive"))
    )
    (net (code "95") (name "unconnected-(U2-P5_5-Pad32)") (class "Default")
      (node (ref "U2") (pin "32") (pinfunction "P5_5_32") (pintype "passive"))
    )
    (net (code "96") (name "unconnected-(U2-P5_6-Pad33)") (class "Default")
      (node (ref "U2") (pin "33") (pinfunction "P5_6_33") (pintype "passive"))
    )
    (net (code "97") (name "unconnected-(U2-P5_7-Pad34)") (class "Default")
      (node (ref "U2") (pin "34") (pinfunction "P5_7_34") (pintype "passive"))
    )
    (net (code "98") (name "unconnected-(U2-P6_4-Pad6)") (class "Default")
      (node (ref "U2") (pin "6") (pinfunction "P6_4_6") (pintype "passive"))
    )
    (net (code "99") (name "unconnected-(U2-P6_5-Pad7)") (class "Default")
      (node (ref "U2") (pin "7") (pinfunction "P6_5_7") (pintype "passive"))
    )
    (net (code "100") (name "unconnected-(U2-P6_6-Pad8)") (class "Default")
      (node (ref "U2") (pin "8") (pinfunction "P6_6_8") (pintype "passive"))
    )
    (net (code "101") (name "unconnected-(U2-P12_0_I2C1_SCL-Pad53)") (class "Default")
      (node (ref "U2") (pin "53") (pinfunction "P12_0_I2C1_SCL_53") (pintype "passive"))
    )
    (net (code "102") (name "unconnected-(U2-P12_1_I2C1_SDA-Pad54)") (class "Default")
      (node (ref "U2") (pin "54") (pinfunction "P12_1_I2C1_SDA_54") (pintype "passive"))
    )
    (net (code "103") (name "unconnected-(U2-P12_2-Pad67)") (class "Default")
      (node (ref "U2") (pin "67") (pinfunction "P12_2_67") (pintype "passive"))
    )
    (net (code "104") (name "unconnected-(U2-P12_3-Pad68)") (class "Default")
      (node (ref "U2") (pin "68") (pinfunction "P12_3_68") (pintype "passive"))
    )
    (net (code "105") (name "unconnected-(U2-P12_6-Pad29)") (class "Default")
      (node (ref "U2") (pin "29") (pinfunction "P12_6_29") (pintype "passive"))
    )
    (net (code "106") (name "unconnected-(U2-P12_7-Pad30)") (class "Default")
      (node (ref "U2") (pin "30") (pinfunction "P12_7_30") (pintype "passive"))
    )
    (net (code "107") (name "unconnected-(U7-PadID)") (class "Default")
      (node (ref "U7") (pin "ID") (pinfunction "ID_ID") (pintype "bidirectional"))
    )
    (net (code "108") (name "unconnected-(U7-SH-PadSH1)") (class "Default")
      (node (ref "U7") (pin "SH1") (pinfunction "SH_SH1") (pintype "bidirectional"))
    )
    (net (code "109") (name "unconnected-(U7-SH-PadSH2)") (class "Default")
      (node (ref "U7") (pin "SH2") (pinfunction "SH_SH2") (pintype "bidirectional"))
    )
    (net (code "110") (name "unconnected-(U7-SH-PadSH3)") (class "Default")
      (node (ref "U7") (pin "SH3") (pinfunction "SH_SH3") (pintype "bidirectional"))
    )
    (net (code "111") (name "unconnected-(U7-SH-PadSH4)") (class "Default")
      (node (ref "U7") (pin "SH4") (pinfunction "SH_SH4") (pintype "bidirectional"))
    )
    (net (code "112") (name "unconnected-(U7-SH-PadSH5)") (class "Default")
      (node (ref "U7") (pin "SH5") (pinfunction "SH_SH5") (pintype "bidirectional"))
    )
    (net (code "113") (name "unconnected-(U7-SH-PadSH6)") (class "Default")
      (node (ref "U7") (pin "SH6") (pinfunction "SH_SH6") (pintype "bidirectional"))
    )
  )
)
